# agrosavia_pcb.net
KiCad netlist of a schematic drawn in EAGLE
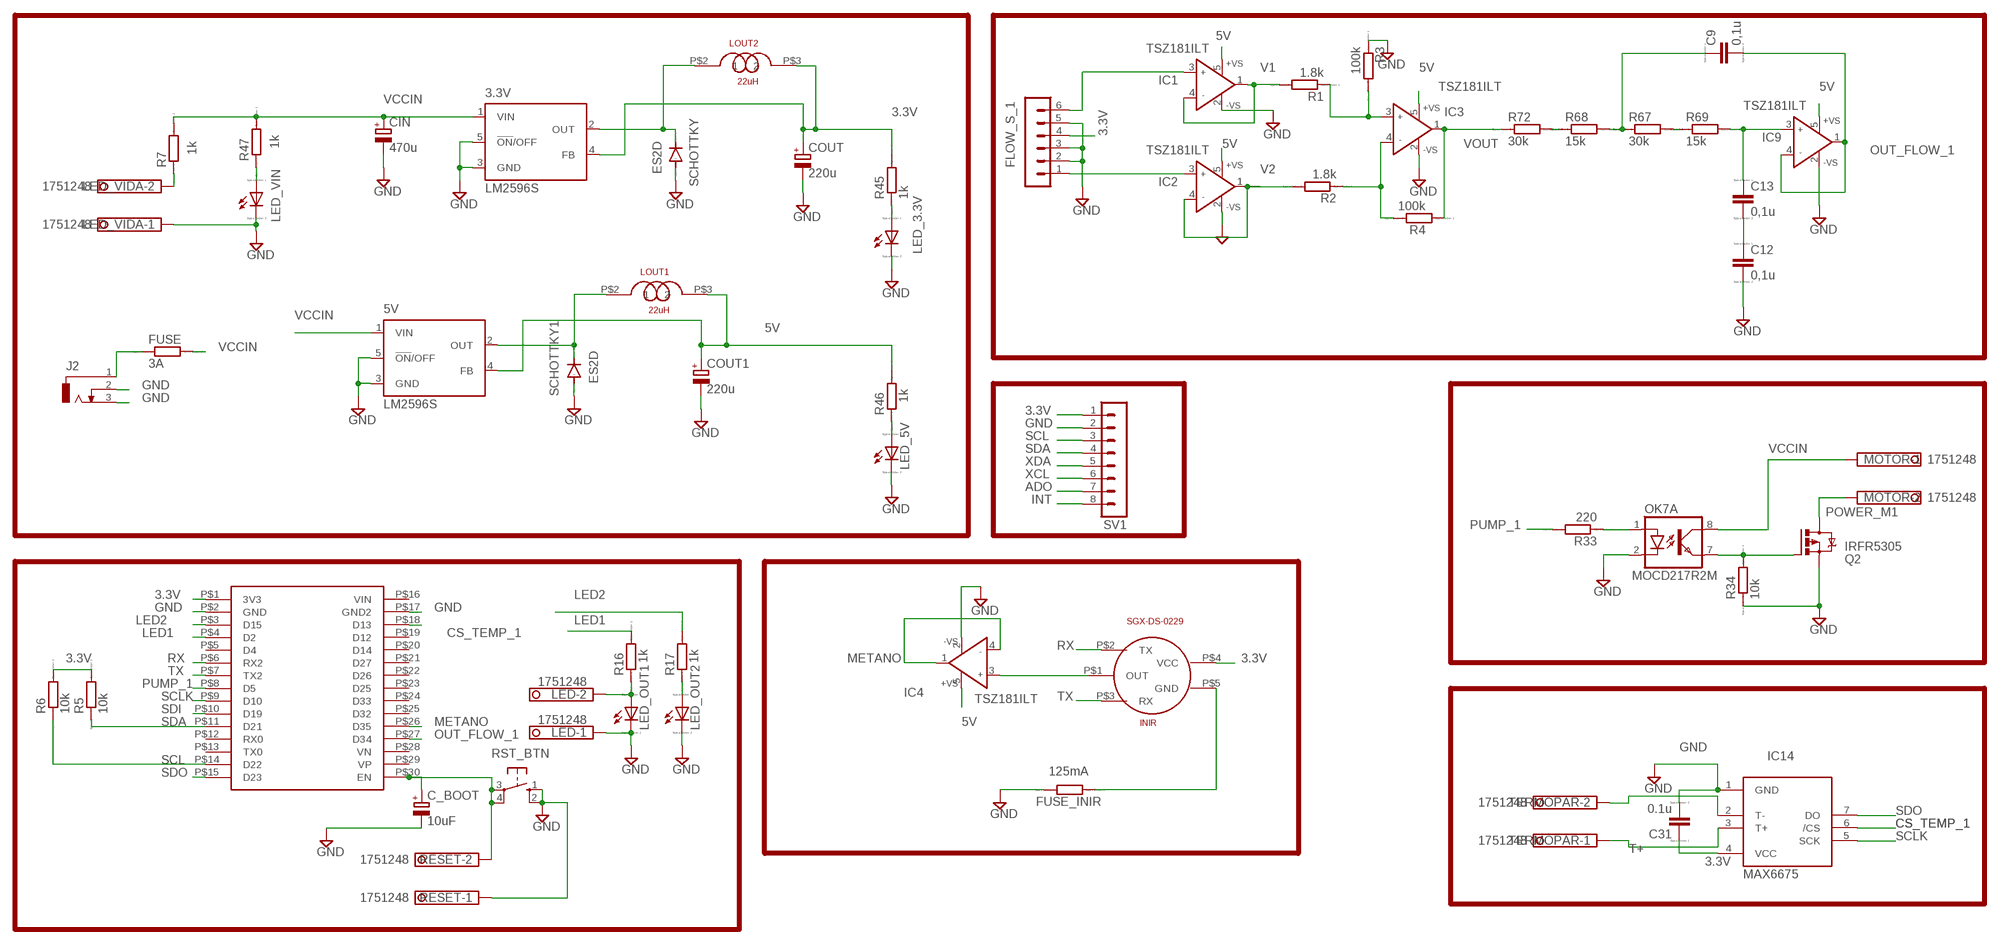
[diagram p0: schematic, sheet 1]

(export (version "E")
  (design (tool "Eeschema 10.0.6"))
  (components
    (comp (ref "3.3V")
      (value "LM2596S")
      (footprint "eagle-import:TO263-5")
      (fields (field (name "MF") "NATIONAL SEMICONDUCTOR") (field (name "MPN") "LM2596S-ADJ/NOPB"))
      (libsource (lib "eagle-import") (part "LM2596S"))
    )
    (comp (ref "5V")
      (value "LM2596S")
      (footprint "eagle-import:TO263-5")
      (fields (field (name "MF") "NATIONAL SEMICONDUCTOR") (field (name "MPN") "LM2596S-ADJ/NOPB"))
      (libsource (lib "eagle-import") (part "LM2596S"))
    )
    (comp (ref "C9")
      (value "0,1u")
      (footprint "eagle-import:C0805")
      (libsource (lib "eagle-import") (part "C"))
    )
    (comp (ref "C12")
      (value "0,1u")
      (footprint "eagle-import:C0805")
      (libsource (lib "eagle-import") (part "C"))
    )
    (comp (ref "C13")
      (value "0,1u")
      (footprint "eagle-import:C0805")
      (libsource (lib "eagle-import") (part "C"))
    )
    (comp (ref "C31")
      (value "0.1u")
      (footprint "eagle-import:C0805")
      (libsource (lib "eagle-import") (part "C"))
    )
    (comp (ref "CIN")
      (value "470u")
      (footprint "eagle-import:SANYO-OSCON_SMD_F12")
      (libsource (lib "eagle-import") (part "CPOL-EUSANYO_SMD_F12"))
    )
    (comp (ref "COUT")
      (value "220u")
      (footprint "eagle-import:UD-10X10_NICHICON")
      (libsource (lib "eagle-import") (part "CPOL-EUUD-10X10"))
    )
    (comp (ref "COUT1")
      (value "220u")
      (footprint "eagle-import:UD-10X10_NICHICON")
      (libsource (lib "eagle-import") (part "CPOL-EUUD-10X10"))
    )
    (comp (ref "C_BOOT")
      (value "10uF")
      (footprint "eagle-import:SANYO-OSCON_SMD_B6")
      (libsource (lib "eagle-import") (part "CPOL-EUSANYO_SMD_B6"))
    )
    (comp (ref "ESP32DEVKITV1")
      (value "ESP32")
      (footprint "eagle-import:ESP32")
      (libsource (lib "eagle-import") (part "ESP32"))
    )
    (comp (ref "FLOW_S_1")
      (value "MA06-1")
      (footprint "eagle-import:MA06-1")
      (libsource (lib "eagle-import") (part "MA06-1"))
    )
    (comp (ref "FUSE")
      (value "3A")
      (footprint "eagle-import:R1206")
      (libsource (lib "eagle-import") (part "RR1206"))
    )
    (comp (ref "FUSE_INIR")
      (value "125mA")
      (footprint "eagle-import:R0402")
      (libsource (lib "eagle-import") (part "RR0402"))
    )
    (comp (ref "IC1")
      (value "TSZ181ILT")
      (footprint "eagle-import:SOT23-5")
      (fields (field (name "MF") "ALTERA CORPORATION") (field (name "MPN") "AD8001ARTZ-REEL7"))
      (libsource (lib "eagle-import") (part "AD8001RT"))
    )
    (comp (ref "IC2")
      (value "TSZ181ILT")
      (footprint "eagle-import:SOT23-5")
      (fields (field (name "MF") "ALTERA CORPORATION") (field (name "MPN") "AD8001ARTZ-REEL7"))
      (libsource (lib "eagle-import") (part "AD8001RT"))
    )
    (comp (ref "IC3")
      (value "TSZ181ILT")
      (footprint "eagle-import:SOT23-5")
      (fields (field (name "MF") "ALTERA CORPORATION") (field (name "MPN") "AD8001ARTZ-REEL7"))
      (libsource (lib "eagle-import") (part "AD8001RT"))
    )
    (comp (ref "IC4")
      (value "TSZ181ILT")
      (footprint "eagle-import:SOT23-5")
      (fields (field (name "MF") "ALTERA CORPORATION") (field (name "MPN") "AD8001ARTZ-REEL7"))
      (libsource (lib "eagle-import") (part "AD8001RT"))
    )
    (comp (ref "IC9")
      (value "TSZ181ILT")
      (footprint "eagle-import:SOT23-5")
      (fields (field (name "MF") "ALTERA CORPORATION") (field (name "MPN") "AD8001ARTZ-REEL7"))
      (libsource (lib "eagle-import") (part "AD8001RT"))
    )
    (comp (ref "IC14")
      (value "MAX6675")
      (footprint "eagle-import:SO08")
      (fields (field (name "MF") "Maxim Integrated"))
      (libsource (lib "eagle-import") (part "MAX6675"))
    )
    (comp (ref "J2")
      (value "DCJ0303")
      (footprint "eagle-import:DCJ0303")
      (libsource (lib "eagle-import") (part "DCJ0303"))
    )
    (comp (ref "LED")
      (value "1751248")
      (footprint "eagle-import:1751248")
      (libsource (lib "eagle-import") (part "1751248"))
    )
    (comp (ref "LED_3.3V")
      (value "LED_E")
      (footprint "eagle-import:LED_1206")
      (libsource (lib "eagle-import") (part "LED_E"))
    )
    (comp (ref "LED_5V")
      (value "LED_E")
      (footprint "eagle-import:LED_1206")
      (libsource (lib "eagle-import") (part "LED_E"))
    )
    (comp (ref "LED_OUT1")
      (value "LED_E")
      (footprint "eagle-import:LED_1206")
      (libsource (lib "eagle-import") (part "LED_E"))
    )
    (comp (ref "LED_OUT2")
      (value "LED_E")
      (footprint "eagle-import:LED_1206")
      (libsource (lib "eagle-import") (part "LED_E"))
    )
    (comp (ref "LED_VIDA")
      (value "1751248")
      (footprint "eagle-import:1751248")
      (libsource (lib "eagle-import") (part "1751248"))
    )
    (comp (ref "LED_VIN")
      (value "LED_E")
      (footprint "eagle-import:LED_1206")
      (libsource (lib "eagle-import") (part "LED_E"))
    )
    (comp (ref "LOUT1")
      (value "22uH")
      (footprint "eagle-import:SRP1038A")
      (libsource (lib "eagle-import") (part "SRP1038A"))
    )
    (comp (ref "LOUT2")
      (value "22uH")
      (footprint "eagle-import:SRP1038A")
      (libsource (lib "eagle-import") (part "SRP1038A"))
    )
    (comp (ref "MOTOR")
      (value "1751248")
      (footprint "eagle-import:1751248")
      (libsource (lib "eagle-import") (part "1751248"))
    )
    (comp (ref "OK7")
      (value "MOCD217R2M")
      (footprint "eagle-import:SOIC08")
      (fields (field (name "MF") "VISHAY/TELEFUNKEN") (field (name "MPN") "ILD205T"))
      (libsource (lib "eagle-import") (part "ILD205"))
    )
    (comp (ref "Q2")
      (value "IRFR5305")
      (footprint "eagle-import:D-PAK_TO252AA")
      (libsource (lib "eagle-import") (part "IRF?5305R"))
    )
    (comp (ref "R1")
      (value "1.8k")
      (footprint "eagle-import:R0805")
      (libsource (lib "eagle-import") (part "R"))
    )
    (comp (ref "R2")
      (value "1.8k")
      (footprint "eagle-import:R0805")
      (libsource (lib "eagle-import") (part "R"))
    )
    (comp (ref "R3")
      (value "100k")
      (footprint "eagle-import:R0805")
      (libsource (lib "eagle-import") (part "R"))
    )
    (comp (ref "R4")
      (value "100k")
      (footprint "eagle-import:R0805")
      (libsource (lib "eagle-import") (part "R"))
    )
    (comp (ref "R5")
      (value "10k")
      (footprint "eagle-import:R1206")
      (libsource (lib "eagle-import") (part "RR1206"))
    )
    (comp (ref "R6")
      (value "10k")
      (footprint "eagle-import:R1206")
      (libsource (lib "eagle-import") (part "RR1206"))
    )
    (comp (ref "R7")
      (value "1k")
      (footprint "eagle-import:R0805")
      (libsource (lib "eagle-import") (part "R"))
    )
    (comp (ref "R16")
      (value "1k")
      (footprint "eagle-import:R0805")
      (libsource (lib "eagle-import") (part "R"))
    )
    (comp (ref "R17")
      (value "1k")
      (footprint "eagle-import:R0805")
      (libsource (lib "eagle-import") (part "R"))
    )
    (comp (ref "R33")
      (value "220")
      (footprint "eagle-import:R0603")
      (libsource (lib "eagle-import") (part "RR0603"))
    )
    (comp (ref "R34")
      (value "10k")
      (footprint "eagle-import:R1206")
      (libsource (lib "eagle-import") (part "RR1206"))
    )
    (comp (ref "R45")
      (value "1k")
      (footprint "eagle-import:R0805")
      (libsource (lib "eagle-import") (part "R"))
    )
    (comp (ref "R46")
      (value "1k")
      (footprint "eagle-import:R0805")
      (libsource (lib "eagle-import") (part "R"))
    )
    (comp (ref "R47")
      (value "1k")
      (footprint "eagle-import:R0805")
      (libsource (lib "eagle-import") (part "R"))
    )
    (comp (ref "R67")
      (value "30k")
      (footprint "eagle-import:R0805")
      (libsource (lib "eagle-import") (part "R"))
    )
    (comp (ref "R68")
      (value "15k")
      (footprint "eagle-import:R0805")
      (libsource (lib "eagle-import") (part "R"))
    )
    (comp (ref "R69")
      (value "15k")
      (footprint "eagle-import:R0805")
      (libsource (lib "eagle-import") (part "R"))
    )
    (comp (ref "R72")
      (value "30k")
      (footprint "eagle-import:R0805")
      (libsource (lib "eagle-import") (part "R"))
    )
    (comp (ref "RESET")
      (value "1751248")
      (footprint "eagle-import:1751248")
      (libsource (lib "eagle-import") (part "1751248"))
    )
    (comp (ref "RST_BTN")
      (value "10-XX")
      (footprint "eagle-import:B3F-10XX")
      (fields (field (name "MPN") "B3F-1000"))
      (libsource (lib "eagle-import") (part "10-XX"))
    )
    (comp (ref "SCHOTTKY")
      (value "ES2D")
      (footprint "eagle-import:SMB")
      (libsource (lib "eagle-import") (part "ES2D"))
    )
    (comp (ref "SCHOTTKY1")
      (value "ES2D")
      (footprint "eagle-import:SMB")
      (libsource (lib "eagle-import") (part "ES2D"))
    )
    (comp (ref "SGX-DS-0229")
      (value "INIR")
      (footprint "eagle-import:INIR")
      (libsource (lib "eagle-import") (part "INIR"))
    )
    (comp (ref "SV1")
      (value "MA08-1")
      (footprint "eagle-import:MA08-1")
      (libsource (lib "eagle-import") (part "MA08-1"))
    )
    (comp (ref "TERMOPAR")
      (value "1751248")
      (footprint "eagle-import:1751248")
      (libsource (lib "eagle-import") (part "1751248"))
    )
  )
  (nets
    (net (code "1") (name "/3.3V") (class "Default")
      (node (ref "3.3V") (pin "4") (pinfunction "FB_4") (pintype "input"))
      (node (ref "C31") (pin "1") (pinfunction "1_1") (pintype "passive"))
      (node (ref "COUT") (pin "+") (pinfunction "+_+") (pintype "passive"))
      (node (ref "ESP32DEVKITV1") (pin "P$1") (pinfunction "3V3_P$1") (pintype "bidirectional"))
      (node (ref "FLOW_S_1") (pin "4") (pinfunction "4_4") (pintype "passive"))
      (node (ref "IC14") (pin "4") (pinfunction "VCC_4") (pintype "power_in"))
      (node (ref "LOUT2") (pin "P$3") (pinfunction "2_P$3") (pintype "bidirectional"))
      (node (ref "R45") (pin "2") (pinfunction "2_2") (pintype "passive"))
      (node (ref "R5") (pin "2") (pinfunction "2_2") (pintype "passive"))
      (node (ref "R6") (pin "2") (pinfunction "2_2") (pintype "passive"))
      (node (ref "SGX-DS-0229") (pin "P$4") (pinfunction "VCC_P$4") (pintype "bidirectional"))
      (node (ref "SV1") (pin "1") (pinfunction "1_1") (pintype "passive"))
    )
    (net (code "2") (name "/5V") (class "Default")
      (node (ref "5V") (pin "4") (pinfunction "FB_4") (pintype "input"))
      (node (ref "COUT1") (pin "+") (pinfunction "+_+") (pintype "passive"))
      (node (ref "IC1") (pin "5") (pinfunction "+VS_5") (pintype "input"))
      (node (ref "IC2") (pin "5") (pinfunction "+VS_5") (pintype "input"))
      (node (ref "IC3") (pin "5") (pinfunction "+VS_5") (pintype "input"))
      (node (ref "IC4") (pin "5") (pinfunction "+VS_5") (pintype "input"))
      (node (ref "IC9") (pin "5") (pinfunction "+VS_5") (pintype "input"))
      (node (ref "LOUT1") (pin "P$3") (pinfunction "2_P$3") (pintype "bidirectional"))
      (node (ref "R46") (pin "2") (pinfunction "2_2") (pintype "passive"))
    )
    (net (code "3") (name "/ADO") (class "Default")
      (node (ref "SV1") (pin "7") (pinfunction "7_7") (pintype "passive"))
    )
    (net (code "4") (name "/CS_TEMP_1") (class "Default")
      (node (ref "ESP32DEVKITV1") (pin "P$18") (pinfunction "D13_P$18") (pintype "bidirectional"))
      (node (ref "IC14") (pin "6") (pinfunction "/CS_6") (pintype "input"))
    )
    (net (code "5") (name "/INT") (class "Default")
      (node (ref "SV1") (pin "8") (pinfunction "8_8") (pintype "passive"))
    )
    (net (code "6") (name "/LED1") (class "Default")
      (node (ref "ESP32DEVKITV1") (pin "P$4") (pinfunction "D2_P$4") (pintype "bidirectional"))
      (node (ref "R16") (pin "2") (pinfunction "2_2") (pintype "passive"))
    )
    (net (code "7") (name "/LED2") (class "Default")
      (node (ref "ESP32DEVKITV1") (pin "P$3") (pinfunction "D15_P$3") (pintype "bidirectional"))
      (node (ref "R17") (pin "2") (pinfunction "2_2") (pintype "passive"))
    )
    (net (code "8") (name "/METANO") (class "Default")
      (node (ref "ESP32DEVKITV1") (pin "P$26") (pinfunction "D35_P$26") (pintype "bidirectional"))
      (node (ref "IC4") (pin "1") (pinfunction "OUT_1") (pintype "output"))
      (node (ref "IC4") (pin "4") (pinfunction "IN-_4") (pintype "input"))
    )
    (net (code "9") (name "/OUT_FLOW_1") (class "Default")
      (node (ref "C9") (pin "2") (pinfunction "2_2") (pintype "passive"))
      (node (ref "ESP32DEVKITV1") (pin "P$27") (pinfunction "D34_P$27") (pintype "bidirectional"))
      (node (ref "IC9") (pin "1") (pinfunction "OUT_1") (pintype "output"))
      (node (ref "IC9") (pin "4") (pinfunction "IN-_4") (pintype "input"))
    )
    (net (code "10") (name "/POWER_M1") (class "Default")
      (node (ref "MOTOR") (pin "2") (pinfunction "K_2") (pintype "passive"))
      (node (ref "Q2") (pin "4") (pinfunction "D_4") (pintype "passive"))
    )
    (net (code "11") (name "/PUMP_1") (class "Default")
      (node (ref "ESP32DEVKITV1") (pin "P$8") (pinfunction "D5_P$8") (pintype "bidirectional"))
      (node (ref "R33") (pin "2") (pinfunction "2_2") (pintype "passive"))
    )
    (net (code "12") (name "/RX") (class "Default")
      (node (ref "ESP32DEVKITV1") (pin "P$6") (pinfunction "RX2_P$6") (pintype "bidirectional"))
      (node (ref "SGX-DS-0229") (pin "P$2") (pinfunction "TX_P$2") (pintype "bidirectional"))
    )
    (net (code "13") (name "/SCL") (class "Default")
      (node (ref "ESP32DEVKITV1") (pin "P$14") (pinfunction "D22_P$14") (pintype "bidirectional"))
      (node (ref "R6") (pin "1") (pinfunction "1_1") (pintype "passive"))
      (node (ref "SV1") (pin "3") (pinfunction "3_3") (pintype "passive"))
    )
    (net (code "14") (name "/SCLK") (class "Default")
      (node (ref "ESP32DEVKITV1") (pin "P$9") (pinfunction "D10_P$9") (pintype "bidirectional"))
      (node (ref "IC14") (pin "5") (pinfunction "SCK_5") (pintype "input"))
    )
    (net (code "15") (name "/SDA") (class "Default")
      (node (ref "ESP32DEVKITV1") (pin "P$11") (pinfunction "D21_P$11") (pintype "bidirectional"))
      (node (ref "R5") (pin "1") (pinfunction "1_1") (pintype "passive"))
      (node (ref "SV1") (pin "4") (pinfunction "4_4") (pintype "passive"))
    )
    (net (code "16") (name "/SDI") (class "Default")
      (node (ref "ESP32DEVKITV1") (pin "P$10") (pinfunction "D19_P$10") (pintype "bidirectional"))
    )
    (net (code "17") (name "/SDO") (class "Default")
      (node (ref "ESP32DEVKITV1") (pin "P$15") (pinfunction "D23_P$15") (pintype "bidirectional"))
      (node (ref "IC14") (pin "7") (pinfunction "DO_7") (pintype "output"))
    )
    (net (code "18") (name "/T+") (class "Default")
      (node (ref "IC14") (pin "3") (pinfunction "T+_3") (pintype "input"))
      (node (ref "TERMOPAR") (pin "1") (pinfunction "K_1") (pintype "passive"))
    )
    (net (code "19") (name "/TX") (class "Default")
      (node (ref "ESP32DEVKITV1") (pin "P$7") (pinfunction "TX2_P$7") (pintype "bidirectional"))
      (node (ref "SGX-DS-0229") (pin "P$3") (pinfunction "RX_P$3") (pintype "bidirectional"))
    )
    (net (code "20") (name "/V1") (class "Default")
      (node (ref "IC1") (pin "1") (pinfunction "OUT_1") (pintype "output"))
      (node (ref "IC1") (pin "4") (pinfunction "IN-_4") (pintype "input"))
      (node (ref "R1") (pin "2") (pinfunction "2_2") (pintype "passive"))
    )
    (net (code "21") (name "/V2") (class "Default")
      (node (ref "IC2") (pin "1") (pinfunction "OUT_1") (pintype "output"))
      (node (ref "IC2") (pin "4") (pinfunction "IN-_4") (pintype "input"))
      (node (ref "R2") (pin "2") (pinfunction "2_2") (pintype "passive"))
    )
    (net (code "22") (name "/VCCIN") (class "Default")
      (node (ref "3.3V") (pin "1") (pinfunction "VIN_1") (pintype "input"))
      (node (ref "5V") (pin "1") (pinfunction "VIN_1") (pintype "input"))
      (node (ref "CIN") (pin "+") (pinfunction "+_+") (pintype "passive"))
      (node (ref "FUSE") (pin "2") (pinfunction "2_2") (pintype "passive"))
      (node (ref "MOTOR") (pin "1") (pinfunction "K_1") (pintype "passive"))
      (node (ref "OK7") (pin "8") (pinfunction "COL_8") (pintype "passive"))
      (node (ref "R47") (pin "2") (pinfunction "2_2") (pintype "passive"))
      (node (ref "R7") (pin "2") (pinfunction "2_2") (pintype "passive"))
    )
    (net (code "23") (name "/VOUT") (class "Default")
      (node (ref "IC3") (pin "1") (pinfunction "OUT_1") (pintype "output"))
      (node (ref "R4") (pin "1") (pinfunction "1_1") (pintype "passive"))
      (node (ref "R72") (pin "1") (pinfunction "1_1") (pintype "passive"))
    )
    (net (code "24") (name "/XCL") (class "Default")
      (node (ref "SV1") (pin "6") (pinfunction "6_6") (pintype "passive"))
    )
    (net (code "25") (name "/XDA") (class "Default")
      (node (ref "SV1") (pin "5") (pinfunction "5_5") (pintype "passive"))
    )
    (net (code "26") (name "GND") (class "Default")
      (node (ref "3.3V") (pin "3") (pinfunction "GND_3") (pintype "power_in"))
      (node (ref "3.3V") (pin "5") (pinfunction "~{ON}/OFF_5") (pintype "input"))
      (node (ref "5V") (pin "3") (pinfunction "GND_3") (pintype "power_in"))
      (node (ref "5V") (pin "5") (pinfunction "~{ON}/OFF_5") (pintype "input"))
      (node (ref "C12") (pin "2") (pinfunction "2_2") (pintype "passive"))
      (node (ref "C31") (pin "2") (pinfunction "2_2") (pintype "passive"))
      (node (ref "CIN") (pin "-") (pinfunction "-_-") (pintype "passive"))
      (node (ref "COUT") (pin "-") (pinfunction "-_-") (pintype "passive"))
      (node (ref "COUT1") (pin "-") (pinfunction "-_-") (pintype "passive"))
      (node (ref "C_BOOT") (pin "-") (pinfunction "-_-") (pintype "passive"))
      (node (ref "ESP32DEVKITV1") (pin "P$17") (pinfunction "GND2_P$17") (pintype "bidirectional"))
      (node (ref "ESP32DEVKITV1") (pin "P$2") (pinfunction "GND_P$2") (pintype "bidirectional"))
      (node (ref "FLOW_S_1") (pin "2") (pinfunction "2_2") (pintype "passive"))
      (node (ref "FLOW_S_1") (pin "3") (pinfunction "3_3") (pintype "passive"))
      (node (ref "FLOW_S_1") (pin "5") (pinfunction "5_5") (pintype "passive"))
      (node (ref "FUSE_INIR") (pin "2") (pinfunction "2_2") (pintype "passive"))
      (node (ref "IC1") (pin "2") (pinfunction "-VS_2") (pintype "input"))
      (node (ref "IC14") (pin "1") (pinfunction "GND_1") (pintype "power_in"))
      (node (ref "IC2") (pin "2") (pinfunction "-VS_2") (pintype "input"))
      (node (ref "IC3") (pin "2") (pinfunction "-VS_2") (pintype "input"))
      (node (ref "IC4") (pin "2") (pinfunction "-VS_2") (pintype "input"))
      (node (ref "IC9") (pin "2") (pinfunction "-VS_2") (pintype "input"))
      (node (ref "J2") (pin "2") (pinfunction "2_2") (pintype "passive"))
      (node (ref "J2") (pin "3") (pinfunction "3_3") (pintype "passive"))
      (node (ref "LED") (pin "1") (pinfunction "K_1") (pintype "passive"))
      (node (ref "LED_3.3V") (pin "C") (pinfunction "C_C") (pintype "passive"))
      (node (ref "LED_5V") (pin "C") (pinfunction "C_C") (pintype "passive"))
      (node (ref "LED_OUT1") (pin "C") (pinfunction "C_C") (pintype "passive"))
      (node (ref "LED_OUT2") (pin "C") (pinfunction "C_C") (pintype "passive"))
      (node (ref "LED_VIDA") (pin "1") (pinfunction "K_1") (pintype "passive"))
      (node (ref "LED_VIN") (pin "C") (pinfunction "C_C") (pintype "passive"))
      (node (ref "OK7") (pin "2") (pinfunction "C_2") (pintype "passive"))
      (node (ref "Q2") (pin "3") (pinfunction "S_3") (pintype "passive"))
      (node (ref "R3") (pin "1") (pinfunction "1_1") (pintype "passive"))
      (node (ref "R34") (pin "1") (pinfunction "1_1") (pintype "passive"))
      (node (ref "RESET") (pin "1") (pinfunction "K_1") (pintype "passive"))
      (node (ref "RST_BTN") (pin "1") (pinfunction "S_1") (pintype "passive"))
      (node (ref "RST_BTN") (pin "2") (pinfunction "S1_2") (pintype "passive"))
      (node (ref "SCHOTTKY") (pin "A") (pinfunction "A_A") (pintype "passive"))
      (node (ref "SCHOTTKY1") (pin "A") (pinfunction "A_A") (pintype "passive"))
      (node (ref "SV1") (pin "2") (pinfunction "2_2") (pintype "passive"))
    )
    (net (code "27") (name "Net-(3.3V-OUT)") (class "Default")
      (node (ref "3.3V") (pin "2") (pinfunction "OUT_2") (pintype "output"))
      (node (ref "LOUT2") (pin "P$2") (pinfunction "1_P$2") (pintype "bidirectional"))
      (node (ref "SCHOTTKY") (pin "C") (pinfunction "C_C") (pintype "passive"))
    )
    (net (code "28") (name "Net-(5V-OUT)") (class "Default")
      (node (ref "5V") (pin "2") (pinfunction "OUT_2") (pintype "output"))
      (node (ref "LOUT1") (pin "P$2") (pinfunction "1_P$2") (pintype "bidirectional"))
      (node (ref "SCHOTTKY1") (pin "C") (pinfunction "C_C") (pintype "passive"))
    )
    (net (code "29") (name "Net-(C9-Pad1)") (class "Default")
      (node (ref "C9") (pin "1") (pinfunction "1_1") (pintype "passive"))
      (node (ref "R67") (pin "1") (pinfunction "1_1") (pintype "passive"))
      (node (ref "R68") (pin "2") (pinfunction "2_2") (pintype "passive"))
    )
    (net (code "30") (name "Net-(C12-Pad1)") (class "Default")
      (node (ref "C12") (pin "1") (pinfunction "1_1") (pintype "passive"))
      (node (ref "C13") (pin "2") (pinfunction "2_2") (pintype "passive"))
    )
    (net (code "31") (name "Net-(ESP32DEVKITV1-EN)") (class "Default")
      (node (ref "C_BOOT") (pin "+") (pinfunction "+_+") (pintype "passive"))
      (node (ref "ESP32DEVKITV1") (pin "P$30") (pinfunction "EN_P$30") (pintype "bidirectional"))
      (node (ref "RESET") (pin "2") (pinfunction "K_2") (pintype "passive"))
      (node (ref "RST_BTN") (pin "3") (pinfunction "P_3") (pintype "passive"))
      (node (ref "RST_BTN") (pin "4") (pinfunction "P1_4") (pintype "passive"))
    )
    (net (code "32") (name "Net-(FUSE-Pad1)") (class "Default")
      (node (ref "FUSE") (pin "1") (pinfunction "1_1") (pintype "passive"))
      (node (ref "J2") (pin "1") (pinfunction "1_1") (pintype "passive"))
    )
    (net (code "33") (name "Net-(IC1-IN+)") (class "Default")
      (node (ref "FLOW_S_1") (pin "6") (pinfunction "6_6") (pintype "passive"))
      (node (ref "IC1") (pin "3") (pinfunction "IN+_3") (pintype "input"))
    )
    (net (code "34") (name "Net-(IC2-IN+)") (class "Default")
      (node (ref "FLOW_S_1") (pin "1") (pinfunction "1_1") (pintype "passive"))
      (node (ref "IC2") (pin "3") (pinfunction "IN+_3") (pintype "input"))
    )
    (net (code "35") (name "Net-(IC3-IN+)") (class "Default")
      (node (ref "IC3") (pin "3") (pinfunction "IN+_3") (pintype "input"))
      (node (ref "R1") (pin "1") (pinfunction "1_1") (pintype "passive"))
      (node (ref "R3") (pin "2") (pinfunction "2_2") (pintype "passive"))
    )
    (net (code "36") (name "Net-(IC3-IN-)") (class "Default")
      (node (ref "IC3") (pin "4") (pinfunction "IN-_4") (pintype "input"))
      (node (ref "R2") (pin "1") (pinfunction "1_1") (pintype "passive"))
      (node (ref "R4") (pin "2") (pinfunction "2_2") (pintype "passive"))
    )
    (net (code "37") (name "Net-(IC4-IN+)") (class "Default")
      (node (ref "IC4") (pin "3") (pinfunction "IN+_3") (pintype "input"))
      (node (ref "SGX-DS-0229") (pin "P$1") (pinfunction "OUT_P$1") (pintype "bidirectional"))
    )
    (net (code "38") (name "Net-(IC9-IN+)") (class "Default")
      (node (ref "C13") (pin "1") (pinfunction "1_1") (pintype "passive"))
      (node (ref "IC9") (pin "3") (pinfunction "IN+_3") (pintype "input"))
      (node (ref "R69") (pin "2") (pinfunction "2_2") (pintype "passive"))
    )
    (net (code "39") (name "Net-(IC14-T-)") (class "Default")
      (node (ref "IC14") (pin "2") (pinfunction "T-_2") (pintype "input"))
      (node (ref "TERMOPAR") (pin "2") (pinfunction "K_2") (pintype "passive"))
    )
    (net (code "40") (name "Net-(LEDB-K)") (class "Default")
      (node (ref "LED") (pin "2") (pinfunction "K_2") (pintype "passive"))
      (node (ref "LED_OUT1") (pin "A") (pinfunction "A_A") (pintype "passive"))
      (node (ref "R16") (pin "1") (pinfunction "1_1") (pintype "passive"))
    )
    (net (code "41") (name "Net-(LED_3.3V-PadA)") (class "Default")
      (node (ref "LED_3.3V") (pin "A") (pinfunction "A_A") (pintype "passive"))
      (node (ref "R45") (pin "1") (pinfunction "1_1") (pintype "passive"))
    )
    (net (code "42") (name "Net-(LED_5V-PadA)") (class "Default")
      (node (ref "LED_5V") (pin "A") (pinfunction "A_A") (pintype "passive"))
      (node (ref "R46") (pin "1") (pinfunction "1_1") (pintype "passive"))
    )
    (net (code "43") (name "Net-(LED_OUT2-PadA)") (class "Default")
      (node (ref "LED_OUT2") (pin "A") (pinfunction "A_A") (pintype "passive"))
      (node (ref "R17") (pin "1") (pinfunction "1_1") (pintype "passive"))
    )
    (net (code "44") (name "Net-(LED_VIDAB-K)") (class "Default")
      (node (ref "LED_VIDA") (pin "2") (pinfunction "K_2") (pintype "passive"))
      (node (ref "R7") (pin "1") (pinfunction "1_1") (pintype "passive"))
    )
    (net (code "45") (name "Net-(LED_VIN-PadA)") (class "Default")
      (node (ref "LED_VIN") (pin "A") (pinfunction "A_A") (pintype "passive"))
      (node (ref "R47") (pin "1") (pinfunction "1_1") (pintype "passive"))
    )
    (net (code "46") (name "Net-(OK7A-A)") (class "Default")
      (node (ref "OK7") (pin "1") (pinfunction "A_1") (pintype "passive"))
      (node (ref "R33") (pin "1") (pinfunction "1_1") (pintype "passive"))
    )
    (net (code "47") (name "Net-(OK7A-EMIT)") (class "Default")
      (node (ref "OK7") (pin "7") (pinfunction "EMIT_7") (pintype "passive"))
      (node (ref "Q2") (pin "1") (pinfunction "G_1") (pintype "passive"))
      (node (ref "R34") (pin "2") (pinfunction "2_2") (pintype "passive"))
    )
    (net (code "48") (name "Net-(R67-Pad2)") (class "Default")
      (node (ref "R67") (pin "2") (pinfunction "2_2") (pintype "passive"))
      (node (ref "R69") (pin "1") (pinfunction "1_1") (pintype "passive"))
    )
    (net (code "49") (name "Net-(R68-Pad1)") (class "Default")
      (node (ref "R68") (pin "1") (pinfunction "1_1") (pintype "passive"))
      (node (ref "R72") (pin "2") (pinfunction "2_2") (pintype "passive"))
    )
    (net (code "50") (name "Net-(SGX-DS-0229-GND)") (class "Default")
      (node (ref "FUSE_INIR") (pin "1") (pinfunction "1_1") (pintype "passive"))
      (node (ref "SGX-DS-0229") (pin "P$5") (pinfunction "GND_P$5") (pintype "bidirectional"))
    )
    (net (code "51") (name "unconnected-(ESP32DEVKITV1-D4-PadP$5)") (class "Default")
      (node (ref "ESP32DEVKITV1") (pin "P$5") (pinfunction "D4_P$5") (pintype "bidirectional"))
    )
    (net (code "52") (name "unconnected-(ESP32DEVKITV1-D12-PadP$19)") (class "Default")
      (node (ref "ESP32DEVKITV1") (pin "P$19") (pinfunction "D12_P$19") (pintype "bidirectional"))
    )
    (net (code "53") (name "unconnected-(ESP32DEVKITV1-D14-PadP$20)") (class "Default")
      (node (ref "ESP32DEVKITV1") (pin "P$20") (pinfunction "D14_P$20") (pintype "bidirectional"))
    )
    (net (code "54") (name "unconnected-(ESP32DEVKITV1-D25-PadP$23)") (class "Default")
      (node (ref "ESP32DEVKITV1") (pin "P$23") (pinfunction "D25_P$23") (pintype "bidirectional"))
    )
    (net (code "55") (name "unconnected-(ESP32DEVKITV1-D26-PadP$22)") (class "Default")
      (node (ref "ESP32DEVKITV1") (pin "P$22") (pinfunction "D26_P$22") (pintype "bidirectional"))
    )
    (net (code "56") (name "unconnected-(ESP32DEVKITV1-D27-PadP$21)") (class "Default")
      (node (ref "ESP32DEVKITV1") (pin "P$21") (pinfunction "D27_P$21") (pintype "bidirectional"))
    )
    (net (code "57") (name "unconnected-(ESP32DEVKITV1-D32-PadP$25)") (class "Default")
      (node (ref "ESP32DEVKITV1") (pin "P$25") (pinfunction "D32_P$25") (pintype "bidirectional"))
    )
    (net (code "58") (name "unconnected-(ESP32DEVKITV1-D33-PadP$24)") (class "Default")
      (node (ref "ESP32DEVKITV1") (pin "P$24") (pinfunction "D33_P$24") (pintype "bidirectional"))
    )
    (net (code "59") (name "unconnected-(ESP32DEVKITV1-RX0-PadP$12)") (class "Default")
      (node (ref "ESP32DEVKITV1") (pin "P$12") (pinfunction "RX0_P$12") (pintype "bidirectional"))
    )
    (net (code "60") (name "unconnected-(ESP32DEVKITV1-TX0-PadP$13)") (class "Default")
      (node (ref "ESP32DEVKITV1") (pin "P$13") (pinfunction "TX0_P$13") (pintype "bidirectional"))
    )
    (net (code "61") (name "unconnected-(ESP32DEVKITV1-VIN-PadP$16)") (class "Default")
      (node (ref "ESP32DEVKITV1") (pin "P$16") (pinfunction "VIN_P$16") (pintype "bidirectional"))
    )
    (net (code "62") (name "unconnected-(ESP32DEVKITV1-VN-PadP$28)") (class "Default")
      (node (ref "ESP32DEVKITV1") (pin "P$28") (pinfunction "VN_P$28") (pintype "bidirectional"))
    )
    (net (code "63") (name "unconnected-(ESP32DEVKITV1-VP-PadP$29)") (class "Default")
      (node (ref "ESP32DEVKITV1") (pin "P$29") (pinfunction "VP_P$29") (pintype "bidirectional"))
    )
  )
)
